# Schematic_-_Power_Driver.net
KiCad netlist of a schematic drawn in Altium Designer
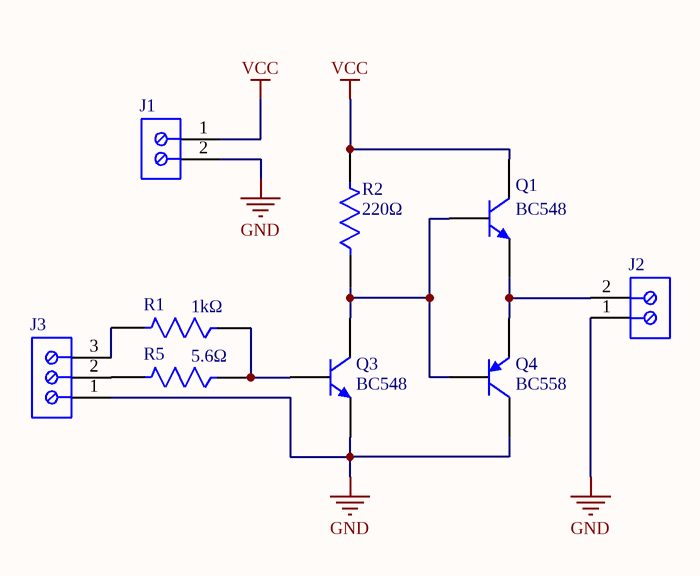
[diagram p0: Schematic - Power Driver.SchDoc]

(export (version "E")
  (design (tool "Eeschema 10.0.6"))
  (components
    (comp (ref "J1")
      (value "1725656")
      (footprint "PHOE-1725656-2")
      (description "Male Header, Pitch 2.54 mm, 1 x 2 Position, Height 9 mm, Tail Length 3.5 mm")
      (fields (field (name "MANUFACTURER") "Phoenix Contact"))
      (libsource (lib "Altium Content Vault") (part "CN-1P-F-TB2"))
    )
    (comp (ref "J2")
      (value "1725656")
      (footprint "PHOE-1725656-2")
      (description "Male Header, Pitch 2.54 mm, 1 x 2 Position, Height 9 mm, Tail Length 3.5 mm")
      (fields (field (name "MANUFACTURER") "Phoenix Contact"))
      (libsource (lib "Altium Content Vault") (part "CN-1P-F-TB2"))
    )
    (comp (ref "J3")
      (value "691214110003")
      (footprint "691214110003")
      (fields (field (name "VOLTAGE") "300V"))
      (libsource (lib "Altium Content Vault") (part "TBL - 1R - 03P - Screw"))
    )
    (comp (ref "Q1")
      (value "BC548")
      (footprint "ONSC-TO-92-3-29-11_AM_BL")
      (description "Amplifier Transistor, NPN Silicon, 3-Pin TO-92, Pb-Free, Tape and Reel")
      (fields (field (name "MANUFACTURER") "On Semiconductor") (field (name "PARTNUMBER") "BC548BRL1G"))
      (libsource (lib "Altium Content Vault") (part "ONSC-NPN-C1B2E3-3"))
    )
    (comp (ref "Q3")
      (value "BC548")
      (footprint "ONSC-TO-92-3-29-11_AM_BL")
      (description "Amplifier Transistor, NPN Silicon, 3-Pin TO-92, Pb-Free, Tape and Reel")
      (fields (field (name "MANUFACTURER") "On Semiconductor") (field (name "PARTNUMBER") "BC548BRL1G"))
      (libsource (lib "Altium Content Vault") (part "ONSC-NPN-C1B2E3-3"))
    )
    (comp (ref "Q4")
      (value "BC558")
      (footprint "ONSC-TO-92-3-29-11_AM_BL")
      (description "Amplifier Transistor, PNP Silicon, 3-Pin TO-92, Pb-Free, Tape and Reel")
      (fields (field (name "MANUFACTURER") "On Semiconductor") (field (name "PARTNUMBER") "BC558BRL1G"))
      (libsource (lib "Altium Content Vault") (part "ONSC-PNP-C1B2E3-3"))
    )
    (comp (ref "R1")
      (value "1kΩ")
      (footprint "FP-CF14-MFG")
      (description "RES 7.5K OHM 1/4W 5% AXIAL")
      (fields (field (name "TOLERANCE") "5%"))
      (libsource (lib "Altium Content Vault") (part "1029c3af85768c4190bb7ad29bc67b5"))
    )
    (comp (ref "R2")
      (value "220Ω")
      (footprint "FP-CF14-MFG")
      (description "RES 7.5K OHM 1/4W 5% AXIAL")
      (fields (field (name "TOLERANCE") "5%"))
      (libsource (lib "Altium Content Vault") (part "1029c3af85768c4190bb7ad29bc67b5"))
    )
    (comp (ref "R5")
      (value "5.6Ω")
      (footprint "FP-CF14-MFG")
      (description "RES 7.5K OHM 1/4W 5% AXIAL")
      (fields (field (name "TOLERANCE") "5%"))
      (libsource (lib "Altium Content Vault") (part "1029c3af85768c4190bb7ad29bc67b5"))
    )
  )
  (nets
    (net (code "1") (name "GND") (class "Default")
      (node (ref "J1") (pin "2") (pinfunction "1_2") (pintype "passive"))
      (node (ref "J2") (pin "1") (pinfunction "2_1") (pintype "passive"))
      (node (ref "J3") (pin "1") (pinfunction "1_1") (pintype "passive"))
      (node (ref "Q3") (pin "3") (pinfunction "E_3") (pintype "passive"))
      (node (ref "Q4") (pin "1") (pinfunction "C_1") (pintype "passive"))
    )
    (net (code "2") (name "Net-(J2-1)") (class "Default")
      (node (ref "J2") (pin "2") (pinfunction "1_2") (pintype "passive"))
      (node (ref "Q1") (pin "3") (pinfunction "E_3") (pintype "passive"))
      (node (ref "Q4") (pin "3") (pinfunction "E_3") (pintype "passive"))
    )
    (net (code "3") (name "Net-(J3-Pad2)") (class "Default")
      (node (ref "J3") (pin "2") (pinfunction "2_2") (pintype "passive"))
      (node (ref "R5") (pin "2") (pinfunction "2_2") (pintype "passive"))
    )
    (net (code "4") (name "Net-(J3-Pad3)") (class "Default")
      (node (ref "J3") (pin "3") (pinfunction "3_3") (pintype "passive"))
      (node (ref "R1") (pin "2") (pinfunction "2_2") (pintype "passive"))
    )
    (net (code "5") (name "Net-(Q1-B)") (class "Default")
      (node (ref "Q1") (pin "2") (pinfunction "B_2") (pintype "passive"))
      (node (ref "Q3") (pin "1") (pinfunction "C_1") (pintype "passive"))
      (node (ref "Q4") (pin "2") (pinfunction "B_2") (pintype "passive"))
      (node (ref "R2") (pin "1") (pinfunction "1_1") (pintype "passive"))
    )
    (net (code "6") (name "Net-(Q3-B)") (class "Default")
      (node (ref "Q3") (pin "2") (pinfunction "B_2") (pintype "passive"))
      (node (ref "R1") (pin "1") (pinfunction "1_1") (pintype "passive"))
      (node (ref "R5") (pin "1") (pinfunction "1_1") (pintype "passive"))
    )
    (net (code "7") (name "VCC") (class "Default")
      (node (ref "J1") (pin "1") (pinfunction "2_1") (pintype "passive"))
      (node (ref "Q1") (pin "1") (pinfunction "C_1") (pintype "passive"))
      (node (ref "R2") (pin "2") (pinfunction "2_2") (pintype "passive"))
    )
  )
)
